# TopPanelV5.net
KiCad netlist of a schematic drawn in EAGLE
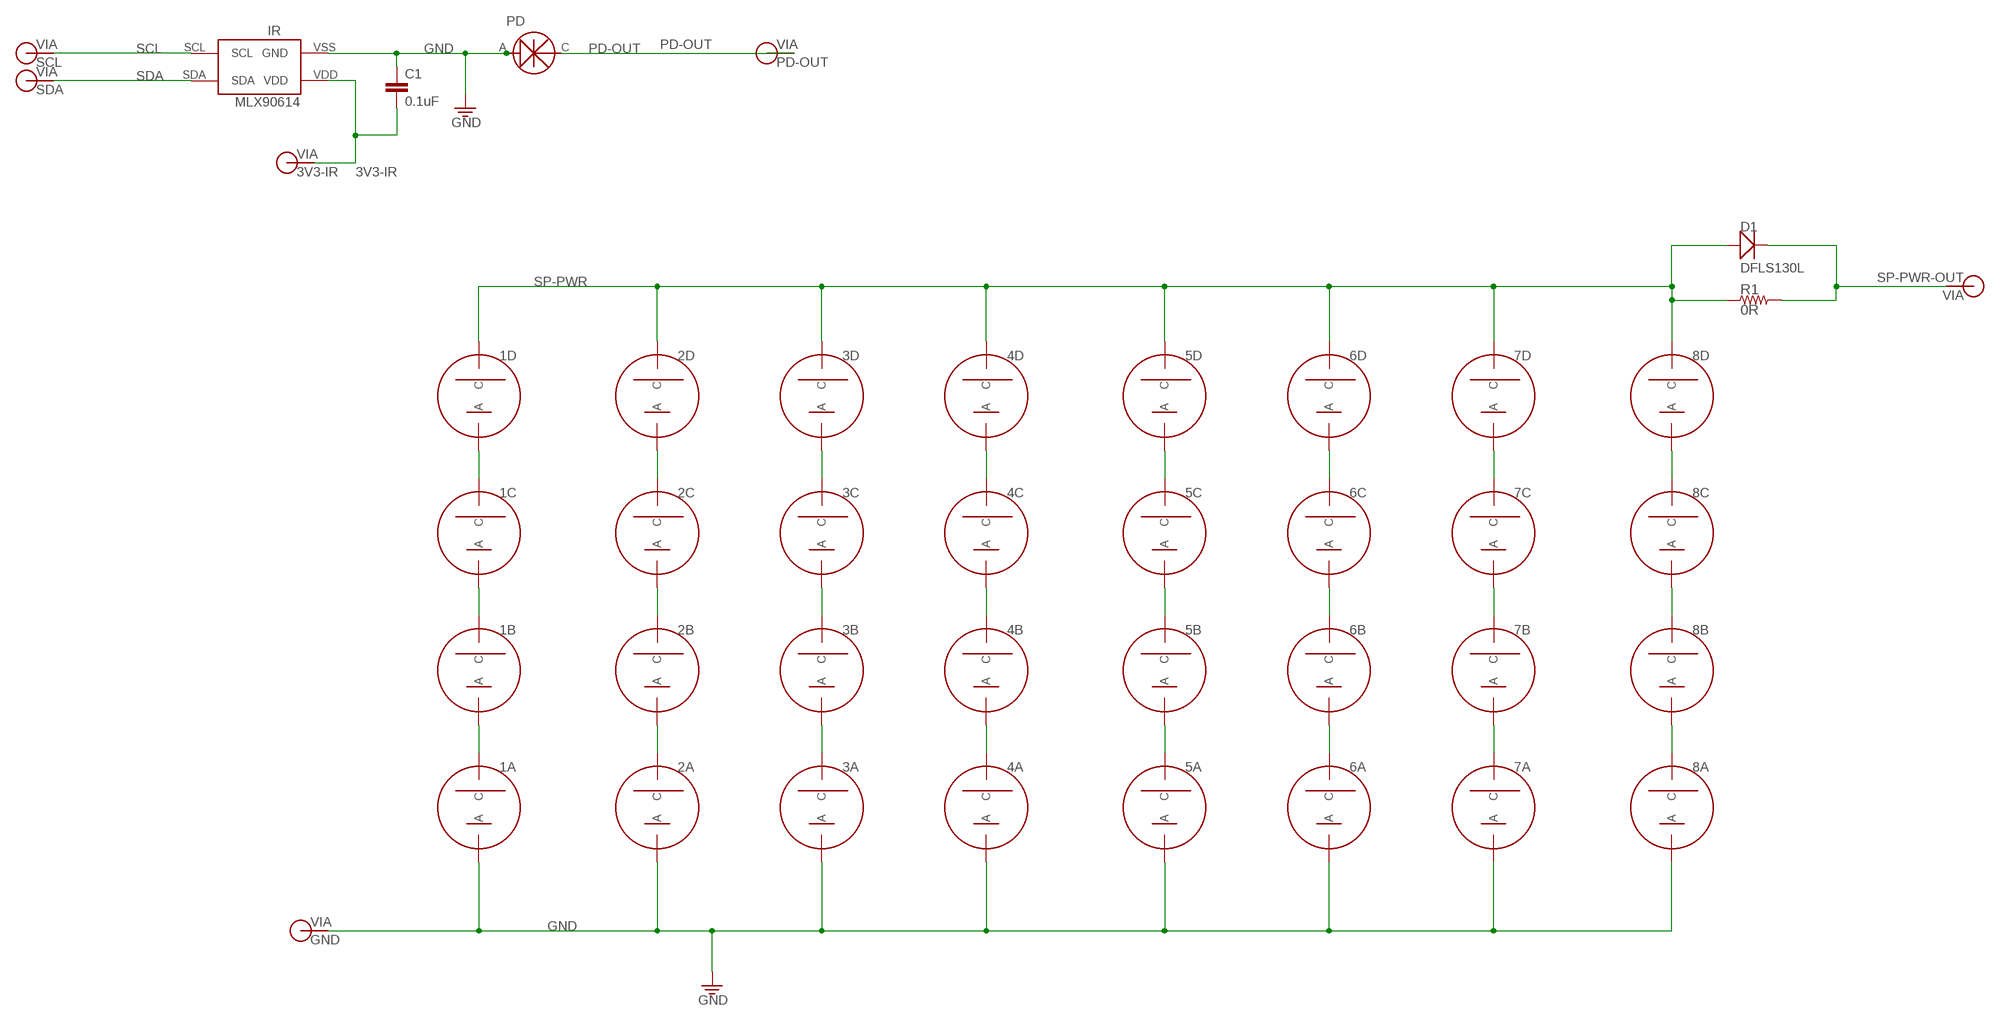
[diagram p0: schematic, sheet 1]

(export (version "E")
  (design (tool "Eeschema 10.0.6"))
  (components
    (comp (ref "1A")
      (value "SOLARCELLV3")
      (footprint "eagle-import:TRISOLX-V3")
      (libsource (lib "eagle-import") (part "SOLARCELLV3"))
    )
    (comp (ref "1B")
      (value "SOLARCELLV3")
      (footprint "eagle-import:TRISOLX-V3")
      (libsource (lib "eagle-import") (part "SOLARCELLV3"))
    )
    (comp (ref "1C")
      (value "SOLARCELLV3")
      (footprint "eagle-import:TRISOLX-V3")
      (libsource (lib "eagle-import") (part "SOLARCELLV3"))
    )
    (comp (ref "1D")
      (value "SOLARCELLV3")
      (footprint "eagle-import:TRISOLX-V3")
      (libsource (lib "eagle-import") (part "SOLARCELLV3"))
    )
    (comp (ref "2A")
      (value "SOLARCELLV3")
      (footprint "eagle-import:TRISOLX-V3")
      (libsource (lib "eagle-import") (part "SOLARCELLV3"))
    )
    (comp (ref "2B")
      (value "SOLARCELLV3")
      (footprint "eagle-import:TRISOLX-V3")
      (libsource (lib "eagle-import") (part "SOLARCELLV3"))
    )
    (comp (ref "2C")
      (value "SOLARCELLV3")
      (footprint "eagle-import:TRISOLX-V3")
      (libsource (lib "eagle-import") (part "SOLARCELLV3"))
    )
    (comp (ref "2D")
      (value "SOLARCELLV3")
      (footprint "eagle-import:TRISOLX-V3")
      (libsource (lib "eagle-import") (part "SOLARCELLV3"))
    )
    (comp (ref "3A")
      (value "SOLARCELLV3")
      (footprint "eagle-import:TRISOLX-V3")
      (libsource (lib "eagle-import") (part "SOLARCELLV3"))
    )
    (comp (ref "3B")
      (value "SOLARCELLV3")
      (footprint "eagle-import:TRISOLX-V3")
      (libsource (lib "eagle-import") (part "SOLARCELLV3"))
    )
    (comp (ref "3C")
      (value "SOLARCELLV3")
      (footprint "eagle-import:TRISOLX-V3")
      (libsource (lib "eagle-import") (part "SOLARCELLV3"))
    )
    (comp (ref "3D")
      (value "SOLARCELLV3")
      (footprint "eagle-import:TRISOLX-V3")
      (libsource (lib "eagle-import") (part "SOLARCELLV3"))
    )
    (comp (ref "4A")
      (value "SOLARCELLV3")
      (footprint "eagle-import:TRISOLX-V3")
      (libsource (lib "eagle-import") (part "SOLARCELLV3"))
    )
    (comp (ref "4B")
      (value "SOLARCELLV3")
      (footprint "eagle-import:TRISOLX-V3")
      (libsource (lib "eagle-import") (part "SOLARCELLV3"))
    )
    (comp (ref "4C")
      (value "SOLARCELLV3")
      (footprint "eagle-import:TRISOLX-V3")
      (libsource (lib "eagle-import") (part "SOLARCELLV3"))
    )
    (comp (ref "4D")
      (value "SOLARCELLV3")
      (footprint "eagle-import:TRISOLX-V3")
      (libsource (lib "eagle-import") (part "SOLARCELLV3"))
    )
    (comp (ref "5A")
      (value "SOLARCELLV3")
      (footprint "eagle-import:TRISOLX-V3")
      (libsource (lib "eagle-import") (part "SOLARCELLV3"))
    )
    (comp (ref "5B")
      (value "SOLARCELLV3")
      (footprint "eagle-import:TRISOLX-V3")
      (libsource (lib "eagle-import") (part "SOLARCELLV3"))
    )
    (comp (ref "5C")
      (value "SOLARCELLV3")
      (footprint "eagle-import:TRISOLX-V3")
      (libsource (lib "eagle-import") (part "SOLARCELLV3"))
    )
    (comp (ref "5D")
      (value "SOLARCELLV3")
      (footprint "eagle-import:TRISOLX-V3")
      (libsource (lib "eagle-import") (part "SOLARCELLV3"))
    )
    (comp (ref "6A")
      (value "SOLARCELLV3")
      (footprint "eagle-import:TRISOLX-V3")
      (libsource (lib "eagle-import") (part "SOLARCELLV3"))
    )
    (comp (ref "6B")
      (value "SOLARCELLV3")
      (footprint "eagle-import:TRISOLX-V3")
      (libsource (lib "eagle-import") (part "SOLARCELLV3"))
    )
    (comp (ref "6C")
      (value "SOLARCELLV3")
      (footprint "eagle-import:TRISOLX-V3")
      (libsource (lib "eagle-import") (part "SOLARCELLV3"))
    )
    (comp (ref "6D")
      (value "SOLARCELLV3")
      (footprint "eagle-import:TRISOLX-V3")
      (libsource (lib "eagle-import") (part "SOLARCELLV3"))
    )
    (comp (ref "7A")
      (value "SOLARCELLV3")
      (footprint "eagle-import:TRISOLX-V3")
      (libsource (lib "eagle-import") (part "SOLARCELLV3"))
    )
    (comp (ref "7B")
      (value "SOLARCELLV3")
      (footprint "eagle-import:TRISOLX-V3")
      (libsource (lib "eagle-import") (part "SOLARCELLV3"))
    )
    (comp (ref "7C")
      (value "SOLARCELLV3")
      (footprint "eagle-import:TRISOLX-V3")
      (libsource (lib "eagle-import") (part "SOLARCELLV3"))
    )
    (comp (ref "7D")
      (value "SOLARCELLV3")
      (footprint "eagle-import:TRISOLX-V3")
      (libsource (lib "eagle-import") (part "SOLARCELLV3"))
    )
    (comp (ref "8A")
      (value "SOLARCELLV3")
      (footprint "eagle-import:TRISOLX-V3")
      (libsource (lib "eagle-import") (part "SOLARCELLV3"))
    )
    (comp (ref "8B")
      (value "SOLARCELLV3")
      (footprint "eagle-import:TRISOLX-V3")
      (libsource (lib "eagle-import") (part "SOLARCELLV3"))
    )
    (comp (ref "8C")
      (value "SOLARCELLV3")
      (footprint "eagle-import:TRISOLX-V3")
      (libsource (lib "eagle-import") (part "SOLARCELLV3"))
    )
    (comp (ref "8D")
      (value "SOLARCELLV3")
      (footprint "eagle-import:TRISOLX-V3")
      (libsource (lib "eagle-import") (part "SOLARCELLV3"))
    )
    (comp (ref "C1")
      (value "0.1uF")
      (footprint "eagle-import:0805")
      (libsource (lib "eagle-import") (part "CAP0805"))
    )
    (comp (ref "D1")
      (value "DFLS130L")
      (footprint "eagle-import:PWRDI-123")
      (libsource (lib "eagle-import") (part "DFLS130L"))
    )
    (comp (ref "IR")
      (value "MXL90614")
      (footprint "eagle-import:MXL90620")
      (libsource (lib "eagle-import") (part "MXL90614"))
    )
    (comp (ref "PD")
      (value "TEMD6200")
      (footprint "eagle-import:TEMD6200")
      (libsource (lib "eagle-import") (part "TEMD6200"))
    )
    (comp (ref "R1")
      (value "0R")
      (footprint "eagle-import:1210")
      (libsource (lib "eagle-import") (part "RES1210"))
    )
    (comp (ref "SCL")
      (value "SCL")
      (footprint "eagle-import:VIA-60MIL")
      (libsource (lib "eagle-import") (part "VIA-60MIL"))
    )
    (comp (ref "SDA")
      (value "SDA")
      (footprint "eagle-import:VIA-60MIL")
      (libsource (lib "eagle-import") (part "VIA-60MIL"))
    )
    (comp (ref "V1")
      (value "SP-PWR-OUT")
      (footprint "eagle-import:VIA-60MIL")
      (libsource (lib "eagle-import") (part "VIA-60MIL"))
    )
    (comp (ref "V3")
      (value "3V3-IR")
      (footprint "eagle-import:VIA-60MIL")
      (libsource (lib "eagle-import") (part "VIA-60MIL"))
    )
    (comp (ref "V4")
      (value "GND")
      (footprint "eagle-import:VIA-60MIL")
      (libsource (lib "eagle-import") (part "VIA-60MIL"))
    )
    (comp (ref "V6")
      (value "PD-OUT")
      (footprint "eagle-import:VIA-60MIL")
      (libsource (lib "eagle-import") (part "VIA-60MIL"))
    )
  )
  (nets
    (net (code "1") (name "/3V3-IR") (class "Default")
      (node (ref "C1") (pin "2") (pinfunction "2_2") (pintype "passive"))
      (node (ref "IR") (pin "VDD") (pinfunction "VDD_VDD") (pintype "bidirectional"))
      (node (ref "V3") (pin "P$1") (pinfunction "P$1_P$1") (pintype "bidirectional"))
    )
    (net (code "2") (name "/PD-OUT") (class "Default")
      (node (ref "PD") (pin "C") (pinfunction "C_C") (pintype "bidirectional"))
      (node (ref "V6") (pin "P$1") (pinfunction "P$1_P$1") (pintype "bidirectional"))
    )
    (net (code "3") (name "/SCL") (class "Default")
      (node (ref "IR") (pin "SCL") (pinfunction "SCL_SCL") (pintype "bidirectional"))
      (node (ref "SCL") (pin "P$1") (pinfunction "P$1_P$1") (pintype "bidirectional"))
    )
    (net (code "4") (name "/SDA") (class "Default")
      (node (ref "IR") (pin "SDA") (pinfunction "SDA_SDA") (pintype "bidirectional"))
      (node (ref "SDA") (pin "P$1") (pinfunction "P$1_P$1") (pintype "bidirectional"))
    )
    (net (code "5") (name "/SP-PWR") (class "Default")
      (node (ref "1D") (pin "CATHODE") (pinfunction "C_CATHODE") (pintype "bidirectional"))
      (node (ref "2D") (pin "CATHODE") (pinfunction "C_CATHODE") (pintype "bidirectional"))
      (node (ref "3D") (pin "CATHODE") (pinfunction "C_CATHODE") (pintype "bidirectional"))
      (node (ref "4D") (pin "CATHODE") (pinfunction "C_CATHODE") (pintype "bidirectional"))
      (node (ref "5D") (pin "CATHODE") (pinfunction "C_CATHODE") (pintype "bidirectional"))
      (node (ref "6D") (pin "CATHODE") (pinfunction "C_CATHODE") (pintype "bidirectional"))
      (node (ref "7D") (pin "CATHODE") (pinfunction "C_CATHODE") (pintype "bidirectional"))
      (node (ref "8D") (pin "CATHODE") (pinfunction "C_CATHODE") (pintype "bidirectional"))
      (node (ref "D1") (pin "A") (pinfunction "A_A") (pintype "bidirectional"))
      (node (ref "R1") (pin "P$1") (pinfunction "1_P$1") (pintype "passive"))
    )
    (net (code "6") (name "GND") (class "Default")
      (node (ref "1A") (pin "ANODE") (pinfunction "A_ANODE") (pintype "bidirectional"))
      (node (ref "2A") (pin "ANODE") (pinfunction "A_ANODE") (pintype "bidirectional"))
      (node (ref "3A") (pin "ANODE") (pinfunction "A_ANODE") (pintype "bidirectional"))
      (node (ref "4A") (pin "ANODE") (pinfunction "A_ANODE") (pintype "bidirectional"))
      (node (ref "5A") (pin "ANODE") (pinfunction "A_ANODE") (pintype "bidirectional"))
      (node (ref "6A") (pin "ANODE") (pinfunction "A_ANODE") (pintype "bidirectional"))
      (node (ref "7A") (pin "ANODE") (pinfunction "A_ANODE") (pintype "bidirectional"))
      (node (ref "8A") (pin "ANODE") (pinfunction "A_ANODE") (pintype "bidirectional"))
      (node (ref "C1") (pin "1") (pinfunction "1_1") (pintype "passive"))
      (node (ref "IR") (pin "VSS") (pinfunction "GND_VSS") (pintype "bidirectional"))
      (node (ref "PD") (pin "A") (pinfunction "A_A") (pintype "bidirectional"))
      (node (ref "V4") (pin "P$1") (pinfunction "P$1_P$1") (pintype "bidirectional"))
    )
    (net (code "7") (name "Net-(1A-C)") (class "Default")
      (node (ref "1A") (pin "CATHODE") (pinfunction "C_CATHODE") (pintype "bidirectional"))
      (node (ref "1B") (pin "ANODE") (pinfunction "A_ANODE") (pintype "bidirectional"))
    )
    (net (code "8") (name "Net-(1B-C)") (class "Default")
      (node (ref "1B") (pin "CATHODE") (pinfunction "C_CATHODE") (pintype "bidirectional"))
      (node (ref "1C") (pin "ANODE") (pinfunction "A_ANODE") (pintype "bidirectional"))
    )
    (net (code "9") (name "Net-(1C-C)") (class "Default")
      (node (ref "1C") (pin "CATHODE") (pinfunction "C_CATHODE") (pintype "bidirectional"))
      (node (ref "1D") (pin "ANODE") (pinfunction "A_ANODE") (pintype "bidirectional"))
    )
    (net (code "10") (name "Net-(2A-C)") (class "Default")
      (node (ref "2A") (pin "CATHODE") (pinfunction "C_CATHODE") (pintype "bidirectional"))
      (node (ref "2B") (pin "ANODE") (pinfunction "A_ANODE") (pintype "bidirectional"))
    )
    (net (code "11") (name "Net-(2B-C)") (class "Default")
      (node (ref "2B") (pin "CATHODE") (pinfunction "C_CATHODE") (pintype "bidirectional"))
      (node (ref "2C") (pin "ANODE") (pinfunction "A_ANODE") (pintype "bidirectional"))
    )
    (net (code "12") (name "Net-(2C-C)") (class "Default")
      (node (ref "2C") (pin "CATHODE") (pinfunction "C_CATHODE") (pintype "bidirectional"))
      (node (ref "2D") (pin "ANODE") (pinfunction "A_ANODE") (pintype "bidirectional"))
    )
    (net (code "13") (name "Net-(3A-C)") (class "Default")
      (node (ref "3A") (pin "CATHODE") (pinfunction "C_CATHODE") (pintype "bidirectional"))
      (node (ref "3B") (pin "ANODE") (pinfunction "A_ANODE") (pintype "bidirectional"))
    )
    (net (code "14") (name "Net-(3B-C)") (class "Default")
      (node (ref "3B") (pin "CATHODE") (pinfunction "C_CATHODE") (pintype "bidirectional"))
      (node (ref "3C") (pin "ANODE") (pinfunction "A_ANODE") (pintype "bidirectional"))
    )
    (net (code "15") (name "Net-(3C-C)") (class "Default")
      (node (ref "3C") (pin "CATHODE") (pinfunction "C_CATHODE") (pintype "bidirectional"))
      (node (ref "3D") (pin "ANODE") (pinfunction "A_ANODE") (pintype "bidirectional"))
    )
    (net (code "16") (name "Net-(4A-C)") (class "Default")
      (node (ref "4A") (pin "CATHODE") (pinfunction "C_CATHODE") (pintype "bidirectional"))
      (node (ref "4B") (pin "ANODE") (pinfunction "A_ANODE") (pintype "bidirectional"))
    )
    (net (code "17") (name "Net-(4B-C)") (class "Default")
      (node (ref "4B") (pin "CATHODE") (pinfunction "C_CATHODE") (pintype "bidirectional"))
      (node (ref "4C") (pin "ANODE") (pinfunction "A_ANODE") (pintype "bidirectional"))
    )
    (net (code "18") (name "Net-(4C-C)") (class "Default")
      (node (ref "4C") (pin "CATHODE") (pinfunction "C_CATHODE") (pintype "bidirectional"))
      (node (ref "4D") (pin "ANODE") (pinfunction "A_ANODE") (pintype "bidirectional"))
    )
    (net (code "19") (name "Net-(5A-C)") (class "Default")
      (node (ref "5A") (pin "CATHODE") (pinfunction "C_CATHODE") (pintype "bidirectional"))
      (node (ref "5B") (pin "ANODE") (pinfunction "A_ANODE") (pintype "bidirectional"))
    )
    (net (code "20") (name "Net-(5B-C)") (class "Default")
      (node (ref "5B") (pin "CATHODE") (pinfunction "C_CATHODE") (pintype "bidirectional"))
      (node (ref "5C") (pin "ANODE") (pinfunction "A_ANODE") (pintype "bidirectional"))
    )
    (net (code "21") (name "Net-(5C-C)") (class "Default")
      (node (ref "5C") (pin "CATHODE") (pinfunction "C_CATHODE") (pintype "bidirectional"))
      (node (ref "5D") (pin "ANODE") (pinfunction "A_ANODE") (pintype "bidirectional"))
    )
    (net (code "22") (name "Net-(6A-C)") (class "Default")
      (node (ref "6A") (pin "CATHODE") (pinfunction "C_CATHODE") (pintype "bidirectional"))
      (node (ref "6B") (pin "ANODE") (pinfunction "A_ANODE") (pintype "bidirectional"))
    )
    (net (code "23") (name "Net-(6B-C)") (class "Default")
      (node (ref "6B") (pin "CATHODE") (pinfunction "C_CATHODE") (pintype "bidirectional"))
      (node (ref "6C") (pin "ANODE") (pinfunction "A_ANODE") (pintype "bidirectional"))
    )
    (net (code "24") (name "Net-(6C-C)") (class "Default")
      (node (ref "6C") (pin "CATHODE") (pinfunction "C_CATHODE") (pintype "bidirectional"))
      (node (ref "6D") (pin "ANODE") (pinfunction "A_ANODE") (pintype "bidirectional"))
    )
    (net (code "25") (name "Net-(7A-C)") (class "Default")
      (node (ref "7A") (pin "CATHODE") (pinfunction "C_CATHODE") (pintype "bidirectional"))
      (node (ref "7B") (pin "ANODE") (pinfunction "A_ANODE") (pintype "bidirectional"))
    )
    (net (code "26") (name "Net-(7B-C)") (class "Default")
      (node (ref "7B") (pin "CATHODE") (pinfunction "C_CATHODE") (pintype "bidirectional"))
      (node (ref "7C") (pin "ANODE") (pinfunction "A_ANODE") (pintype "bidirectional"))
    )
    (net (code "27") (name "Net-(7C-C)") (class "Default")
      (node (ref "7C") (pin "CATHODE") (pinfunction "C_CATHODE") (pintype "bidirectional"))
      (node (ref "7D") (pin "ANODE") (pinfunction "A_ANODE") (pintype "bidirectional"))
    )
    (net (code "28") (name "Net-(8A-C)") (class "Default")
      (node (ref "8A") (pin "CATHODE") (pinfunction "C_CATHODE") (pintype "bidirectional"))
      (node (ref "8B") (pin "ANODE") (pinfunction "A_ANODE") (pintype "bidirectional"))
    )
    (net (code "29") (name "Net-(8B-C)") (class "Default")
      (node (ref "8B") (pin "CATHODE") (pinfunction "C_CATHODE") (pintype "bidirectional"))
      (node (ref "8C") (pin "ANODE") (pinfunction "A_ANODE") (pintype "bidirectional"))
    )
    (net (code "30") (name "Net-(8C-C)") (class "Default")
      (node (ref "8C") (pin "CATHODE") (pinfunction "C_CATHODE") (pintype "bidirectional"))
      (node (ref "8D") (pin "ANODE") (pinfunction "A_ANODE") (pintype "bidirectional"))
    )
    (net (code "31") (name "Net-(R1-2)") (class "Default")
      (node (ref "D1") (pin "C") (pinfunction "C_C") (pintype "bidirectional"))
      (node (ref "R1") (pin "P$2") (pinfunction "2_P$2") (pintype "passive"))
      (node (ref "V1") (pin "P$1") (pinfunction "P$1_P$1") (pintype "bidirectional"))
    )
  )
)
